# diskohedron4w_hermaphrodit.net
KiCad netlist of a schematic drawn in EAGLE
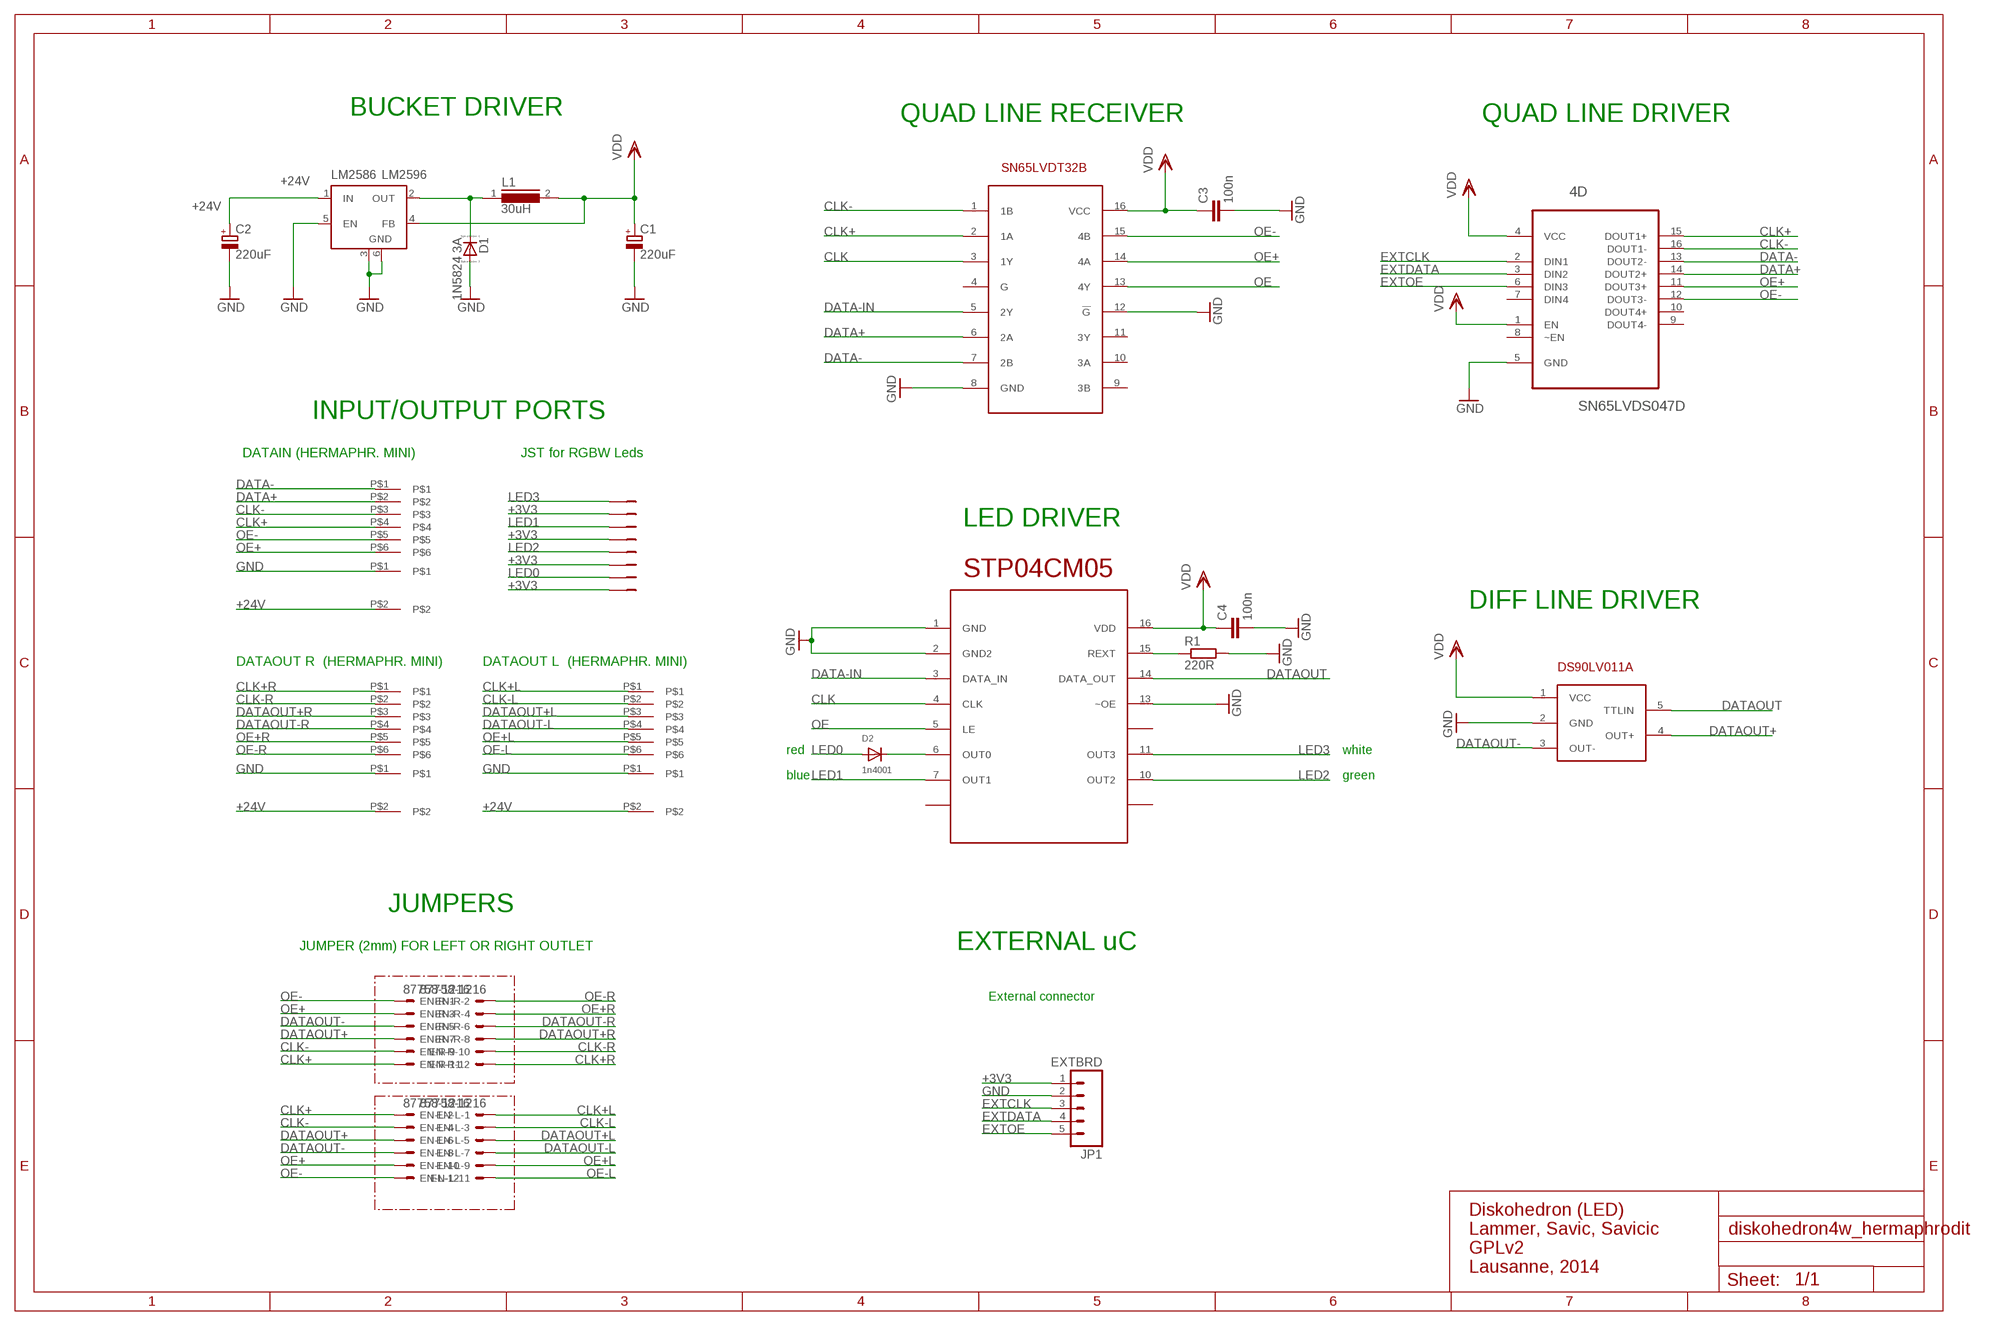
[diagram p0: schematic, sheet 1]

(export (version "E")
  (design (tool "Eeschema 10.0.6"))
  (components
    (comp (ref "1D")
      (value "DS90LV011A")
      (footprint "eagle-import:SOT23-5")
      (libsource (lib "eagle-import") (part "DS90LV011A"))
    )
    (comp (ref "4D")
      (value "SN65LVDS047D")
      (footprint "eagle-import:SOIC127P600X175-16N")
      (libsource (lib "eagle-import") (part "SN65LVDS047D"))
    )
    (comp (ref "4R")
      (value "SN65LVDST32")
      (footprint "eagle-import:SOIC16")
      (libsource (lib "eagle-import") (part "SN65LVDST32"))
    )
    (comp (ref "C1")
      (value "220uF")
      (footprint "eagle-import:153CLV-1010")
      (libsource (lib "eagle-import") (part "CPOL-EU153CLV-1010"))
    )
    (comp (ref "C2")
      (value "220uF")
      (footprint "eagle-import:153CLV-1010")
      (libsource (lib "eagle-import") (part "CPOL-EU153CLV-1010"))
    )
    (comp (ref "C3")
      (value "100n")
      (footprint "eagle-import:C0805")
      (libsource (lib "eagle-import") (part "C-EUC0805"))
    )
    (comp (ref "C4")
      (value "100n")
      (footprint "eagle-import:C0805")
      (libsource (lib "eagle-import") (part "C-EUC0805"))
    )
    (comp (ref "D1")
      (value "1N5824 3A")
      (footprint "eagle-import:DIODE_SMC")
      (libsource (lib "eagle-import") (part "DIODE_E-SMC"))
    )
    (comp (ref "D2")
      (value "1n4001")
      (footprint "eagle-import:SMADIODE")
      (libsource (lib "eagle-import") (part "DIODESMA"))
    )
    (comp (ref "EN-L")
      (value "87758-1216")
      (footprint "eagle-import:87758-1216")
      (libsource (lib "eagle-import") (part "87758-1216"))
    )
    (comp (ref "EN-R")
      (value "87758-1216")
      (footprint "eagle-import:87758-1216")
      (libsource (lib "eagle-import") (part "87758-1216"))
    )
    (comp (ref "IN1")
      (value "HERMAPHRODITMINI6PIN")
      (footprint "eagle-import:HERMAPHRODITMINI6PIN")
      (libsource (lib "eagle-import") (part "HERMAPHRODITMINI6PIN"))
    )
    (comp (ref "JP1")
      (value "EXTBRD")
      (footprint "eagle-import:1X05")
      (libsource (lib "eagle-import") (part "M05PTH"))
    )
    (comp (ref "JST")
      (value "8PIN-ZH")
      (footprint "eagle-import:B8B-ZH")
      (libsource (lib "eagle-import") (part "8PIN-ZH"))
    )
    (comp (ref "L1")
      (value "30uH")
      (footprint "eagle-import:DR127")
      (libsource (lib "eagle-import") (part "DR127"))
    )
    (comp (ref "LM2586")
      (value "LM2596")
      (footprint "eagle-import:TO263-5")
      (libsource (lib "eagle-import") (part "LM2596S"))
    )
    (comp (ref "OUT-L")
      (value "HERMAPHRODITMINI6PIN")
      (footprint "eagle-import:HERMAPHRODITMINI6PIN")
      (libsource (lib "eagle-import") (part "HERMAPHRODITMINI6PIN"))
    )
    (comp (ref "OUT-R")
      (value "HERMAPHRODITMINI6PIN")
      (footprint "eagle-import:HERMAPHRODITMINI6PIN")
      (libsource (lib "eagle-import") (part "HERMAPHRODITMINI6PIN"))
    )
    (comp (ref "R1")
      (value "220R")
      (footprint "eagle-import:M0805")
      (libsource (lib "eagle-import") (part "R-EU_M0805"))
    )
    (comp (ref "STP04")
      (value "STP04CM05")
      (footprint "eagle-import:TSSOP16")
      (libsource (lib "eagle-import") (part "STP04CM05"))
    )
    (comp (ref "U$6")
      (value "HERMAPHRODIT2PIN")
      (footprint "eagle-import:HERMAPHRODIT2PIN")
      (libsource (lib "eagle-import") (part "HERMAPHRODIT2PIN"))
    )
    (comp (ref "U$7")
      (value "HERMAPHRODIT2PIN")
      (footprint "eagle-import:HERMAPHRODIT2PIN")
      (libsource (lib "eagle-import") (part "HERMAPHRODIT2PIN"))
    )
    (comp (ref "U$12")
      (value "HERMAPHRODIT2PIN")
      (footprint "eagle-import:HERMAPHRODIT2PIN")
      (libsource (lib "eagle-import") (part "HERMAPHRODIT2PIN"))
    )
  )
  (nets
    (net (code "1") (name "/+24V") (class "Default")
      (node (ref "C2") (pin "+") (pinfunction "+_+") (pintype "passive"))
      (node (ref "LM2586") (pin "1") (pinfunction "IN_1") (pintype "input"))
      (node (ref "U$12") (pin "P$2") (pinfunction "P$2_P$2") (pintype "bidirectional"))
      (node (ref "U$6") (pin "P$2") (pinfunction "P$2_P$2") (pintype "bidirectional"))
      (node (ref "U$7") (pin "P$2") (pinfunction "P$2_P$2") (pintype "bidirectional"))
    )
    (net (code "2") (name "/CLK") (class "Default")
      (node (ref "4R") (pin "3") (pinfunction "1Y_3") (pintype "bidirectional"))
      (node (ref "STP04") (pin "4") (pinfunction "CLK_4") (pintype "bidirectional"))
    )
    (net (code "3") (name "/CLK+") (class "Default")
      (node (ref "4D") (pin "15") (pinfunction "DOUT1+_15") (pintype "output"))
      (node (ref "4R") (pin "2") (pinfunction "1A_2") (pintype "bidirectional"))
      (node (ref "EN-L") (pin "2") (pinfunction "S_2") (pintype "passive"))
      (node (ref "EN-R") (pin "11") (pinfunction "S_11") (pintype "passive"))
      (node (ref "IN1") (pin "P$4") (pinfunction "P$4_P$4") (pintype "bidirectional"))
    )
    (net (code "4") (name "/CLK+L") (class "Default")
      (node (ref "EN-L") (pin "1") (pinfunction "S_1") (pintype "passive"))
      (node (ref "OUT-L") (pin "P$1") (pinfunction "P$1_P$1") (pintype "bidirectional"))
    )
    (net (code "5") (name "/CLK+R") (class "Default")
      (node (ref "EN-R") (pin "12") (pinfunction "S_12") (pintype "passive"))
      (node (ref "OUT-R") (pin "P$1") (pinfunction "P$1_P$1") (pintype "bidirectional"))
    )
    (net (code "6") (name "/CLK-") (class "Default")
      (node (ref "4D") (pin "16") (pinfunction "DOUT1-_16") (pintype "output"))
      (node (ref "4R") (pin "1") (pinfunction "1B_1") (pintype "bidirectional"))
      (node (ref "EN-L") (pin "4") (pinfunction "S_4") (pintype "passive"))
      (node (ref "EN-R") (pin "9") (pinfunction "S_9") (pintype "passive"))
      (node (ref "IN1") (pin "P$3") (pinfunction "P$3_P$3") (pintype "bidirectional"))
    )
    (net (code "7") (name "/CLK-L") (class "Default")
      (node (ref "EN-L") (pin "3") (pinfunction "S_3") (pintype "passive"))
      (node (ref "OUT-L") (pin "P$2") (pinfunction "P$2_P$2") (pintype "bidirectional"))
    )
    (net (code "8") (name "/CLK-R") (class "Default")
      (node (ref "EN-R") (pin "10") (pinfunction "S_10") (pintype "passive"))
      (node (ref "OUT-R") (pin "P$2") (pinfunction "P$2_P$2") (pintype "bidirectional"))
    )
    (net (code "9") (name "/DATA+") (class "Default")
      (node (ref "4D") (pin "14") (pinfunction "DOUT2+_14") (pintype "output"))
      (node (ref "4R") (pin "6") (pinfunction "2A_6") (pintype "bidirectional"))
      (node (ref "IN1") (pin "P$2") (pinfunction "P$2_P$2") (pintype "bidirectional"))
    )
    (net (code "10") (name "/DATA-") (class "Default")
      (node (ref "4D") (pin "13") (pinfunction "DOUT2-_13") (pintype "output"))
      (node (ref "4R") (pin "7") (pinfunction "2B_7") (pintype "bidirectional"))
      (node (ref "IN1") (pin "P$1") (pinfunction "P$1_P$1") (pintype "bidirectional"))
    )
    (net (code "11") (name "/DATA-IN") (class "Default")
      (node (ref "4R") (pin "5") (pinfunction "2Y_5") (pintype "bidirectional"))
      (node (ref "STP04") (pin "3") (pinfunction "DATA_IN_3") (pintype "bidirectional"))
    )
    (net (code "12") (name "/DATAOUT") (class "Default")
      (node (ref "1D") (pin "5") (pinfunction "TTLIN_5") (pintype "bidirectional"))
      (node (ref "STP04") (pin "14") (pinfunction "DATA_OUT_14") (pintype "bidirectional"))
    )
    (net (code "13") (name "/DATAOUT+") (class "Default")
      (node (ref "1D") (pin "4") (pinfunction "OUT+_4") (pintype "bidirectional"))
      (node (ref "EN-L") (pin "6") (pinfunction "S_6") (pintype "passive"))
      (node (ref "EN-R") (pin "7") (pinfunction "S_7") (pintype "passive"))
    )
    (net (code "14") (name "/DATAOUT+L") (class "Default")
      (node (ref "EN-L") (pin "5") (pinfunction "S_5") (pintype "passive"))
      (node (ref "OUT-L") (pin "P$3") (pinfunction "P$3_P$3") (pintype "bidirectional"))
    )
    (net (code "15") (name "/DATAOUT+R") (class "Default")
      (node (ref "EN-R") (pin "8") (pinfunction "S_8") (pintype "passive"))
      (node (ref "OUT-R") (pin "P$3") (pinfunction "P$3_P$3") (pintype "bidirectional"))
    )
    (net (code "16") (name "/DATAOUT-") (class "Default")
      (node (ref "1D") (pin "3") (pinfunction "OUT-_3") (pintype "bidirectional"))
      (node (ref "EN-L") (pin "8") (pinfunction "S_8") (pintype "passive"))
      (node (ref "EN-R") (pin "5") (pinfunction "S_5") (pintype "passive"))
    )
    (net (code "17") (name "/DATAOUT-L") (class "Default")
      (node (ref "EN-L") (pin "7") (pinfunction "S_7") (pintype "passive"))
      (node (ref "OUT-L") (pin "P$4") (pinfunction "P$4_P$4") (pintype "bidirectional"))
    )
    (net (code "18") (name "/DATAOUT-R") (class "Default")
      (node (ref "EN-R") (pin "6") (pinfunction "S_6") (pintype "passive"))
      (node (ref "OUT-R") (pin "P$4") (pinfunction "P$4_P$4") (pintype "bidirectional"))
    )
    (net (code "19") (name "/EXTCLK") (class "Default")
      (node (ref "4D") (pin "2") (pinfunction "DIN1_2") (pintype "input"))
      (node (ref "JP1") (pin "3") (pinfunction "3_3") (pintype "passive"))
    )
    (net (code "20") (name "/EXTDATA") (class "Default")
      (node (ref "4D") (pin "3") (pinfunction "DIN2_3") (pintype "input"))
      (node (ref "JP1") (pin "4") (pinfunction "4_4") (pintype "passive"))
    )
    (net (code "21") (name "/EXTOE") (class "Default")
      (node (ref "4D") (pin "6") (pinfunction "DIN3_6") (pintype "input"))
      (node (ref "JP1") (pin "5") (pinfunction "5_5") (pintype "passive"))
    )
    (net (code "22") (name "/LED0") (class "Default")
      (node (ref "D2") (pin "A") (pinfunction "A_A") (pintype "passive"))
      (node (ref "JST") (pin "7") (pinfunction "1_7") (pintype "passive"))
    )
    (net (code "23") (name "/LED1") (class "Default")
      (node (ref "JST") (pin "3") (pinfunction "1_3") (pintype "passive"))
      (node (ref "STP04") (pin "7") (pinfunction "OUT1_7") (pintype "bidirectional"))
    )
    (net (code "24") (name "/LED2") (class "Default")
      (node (ref "JST") (pin "5") (pinfunction "1_5") (pintype "passive"))
      (node (ref "STP04") (pin "10") (pinfunction "OUT2_10") (pintype "bidirectional"))
    )
    (net (code "25") (name "/LED3") (class "Default")
      (node (ref "JST") (pin "1") (pinfunction "1_1") (pintype "passive"))
      (node (ref "STP04") (pin "11") (pinfunction "OUT3_11") (pintype "bidirectional"))
    )
    (net (code "26") (name "/OE") (class "Default")
      (node (ref "4R") (pin "13") (pinfunction "4Y_13") (pintype "bidirectional"))
      (node (ref "STP04") (pin "5") (pinfunction "LE_5") (pintype "bidirectional"))
    )
    (net (code "27") (name "/OE+") (class "Default")
      (node (ref "4D") (pin "11") (pinfunction "DOUT3+_11") (pintype "output"))
      (node (ref "4R") (pin "14") (pinfunction "4A_14") (pintype "bidirectional"))
      (node (ref "EN-L") (pin "10") (pinfunction "S_10") (pintype "passive"))
      (node (ref "EN-R") (pin "3") (pinfunction "S_3") (pintype "passive"))
      (node (ref "IN1") (pin "P$6") (pinfunction "P$6_P$6") (pintype "bidirectional"))
    )
    (net (code "28") (name "/OE+L") (class "Default")
      (node (ref "EN-L") (pin "9") (pinfunction "S_9") (pintype "passive"))
      (node (ref "OUT-L") (pin "P$5") (pinfunction "P$5_P$5") (pintype "bidirectional"))
    )
    (net (code "29") (name "/OE+R") (class "Default")
      (node (ref "EN-R") (pin "4") (pinfunction "S_4") (pintype "passive"))
      (node (ref "OUT-R") (pin "P$5") (pinfunction "P$5_P$5") (pintype "bidirectional"))
    )
    (net (code "30") (name "/OE-") (class "Default")
      (node (ref "4D") (pin "12") (pinfunction "DOUT3-_12") (pintype "output"))
      (node (ref "4R") (pin "15") (pinfunction "4B_15") (pintype "bidirectional"))
      (node (ref "EN-L") (pin "12") (pinfunction "S_12") (pintype "passive"))
      (node (ref "EN-R") (pin "1") (pinfunction "S_1") (pintype "passive"))
      (node (ref "IN1") (pin "P$5") (pinfunction "P$5_P$5") (pintype "bidirectional"))
    )
    (net (code "31") (name "/OE-L") (class "Default")
      (node (ref "EN-L") (pin "11") (pinfunction "S_11") (pintype "passive"))
      (node (ref "OUT-L") (pin "P$6") (pinfunction "P$6_P$6") (pintype "bidirectional"))
    )
    (net (code "32") (name "/OE-R") (class "Default")
      (node (ref "EN-R") (pin "2") (pinfunction "S_2") (pintype "passive"))
      (node (ref "OUT-R") (pin "P$6") (pinfunction "P$6_P$6") (pintype "bidirectional"))
    )
    (net (code "33") (name "GND") (class "Default")
      (node (ref "1D") (pin "2") (pinfunction "GND_2") (pintype "bidirectional"))
      (node (ref "4D") (pin "5") (pinfunction "GND_5") (pintype "passive"))
      (node (ref "4R") (pin "12") (pinfunction "~{G}_12") (pintype "bidirectional"))
      (node (ref "4R") (pin "8") (pinfunction "GND_8") (pintype "bidirectional"))
      (node (ref "C1") (pin "-") (pinfunction "-_-") (pintype "passive"))
      (node (ref "C2") (pin "-") (pinfunction "-_-") (pintype "passive"))
      (node (ref "C3") (pin "2") (pinfunction "2_2") (pintype "passive"))
      (node (ref "C4") (pin "2") (pinfunction "2_2") (pintype "passive"))
      (node (ref "D1") (pin "A") (pinfunction "C_A") (pintype "passive"))
      (node (ref "JP1") (pin "2") (pinfunction "2_2") (pintype "passive"))
      (node (ref "LM2586") (pin "3") (pinfunction "GND_3") (pintype "power_in"))
      (node (ref "LM2586") (pin "5") (pinfunction "EN_5") (pintype "input"))
      (node (ref "LM2586") (pin "6") (pinfunction "GND_6") (pintype "power_in"))
      (node (ref "R1") (pin "2") (pinfunction "2_2") (pintype "passive"))
      (node (ref "STP04") (pin "1") (pinfunction "GND_1") (pintype "bidirectional"))
      (node (ref "STP04") (pin "13") (pinfunction "~{OE}_13") (pintype "bidirectional"))
      (node (ref "STP04") (pin "2") (pinfunction "GND2_2") (pintype "bidirectional"))
      (node (ref "U$12") (pin "P$1") (pinfunction "P$1_P$1") (pintype "bidirectional"))
      (node (ref "U$6") (pin "P$1") (pinfunction "P$1_P$1") (pintype "bidirectional"))
      (node (ref "U$7") (pin "P$1") (pinfunction "P$1_P$1") (pintype "bidirectional"))
    )
    (net (code "34") (name "Net-(D1-A)") (class "Default")
      (node (ref "D1") (pin "C") (pinfunction "A_C") (pintype "passive"))
      (node (ref "L1") (pin "1") (pinfunction "1_1") (pintype "passive"))
      (node (ref "LM2586") (pin "2") (pinfunction "OUT_2") (pintype "output"))
    )
    (net (code "35") (name "Net-(STP04-OUT0)") (class "Default")
      (node (ref "D2") (pin "C") (pinfunction "C_C") (pintype "passive"))
      (node (ref "STP04") (pin "6") (pinfunction "OUT0_6") (pintype "bidirectional"))
    )
    (net (code "36") (name "Net-(STP04-REXT)") (class "Default")
      (node (ref "R1") (pin "1") (pinfunction "1_1") (pintype "passive"))
      (node (ref "STP04") (pin "15") (pinfunction "REXT_15") (pintype "bidirectional"))
    )
    (net (code "37") (name "VDD") (class "Default")
      (node (ref "1D") (pin "1") (pinfunction "VCC_1") (pintype "bidirectional"))
      (node (ref "4D") (pin "1") (pinfunction "EN_1") (pintype "input"))
      (node (ref "4D") (pin "4") (pinfunction "VCC_4") (pintype "power_in"))
      (node (ref "4R") (pin "16") (pinfunction "VCC_16") (pintype "bidirectional"))
      (node (ref "C1") (pin "+") (pinfunction "+_+") (pintype "passive"))
      (node (ref "C3") (pin "1") (pinfunction "1_1") (pintype "passive"))
      (node (ref "C4") (pin "1") (pinfunction "1_1") (pintype "passive"))
      (node (ref "JP1") (pin "1") (pinfunction "1_1") (pintype "passive"))
      (node (ref "JST") (pin "2") (pinfunction "1_2") (pintype "passive"))
      (node (ref "JST") (pin "4") (pinfunction "1_4") (pintype "passive"))
      (node (ref "JST") (pin "6") (pinfunction "1_6") (pintype "passive"))
      (node (ref "JST") (pin "8") (pinfunction "1_8") (pintype "passive"))
      (node (ref "L1") (pin "2") (pinfunction "2_2") (pintype "passive"))
      (node (ref "LM2586") (pin "4") (pinfunction "FB_4") (pintype "input"))
      (node (ref "STP04") (pin "16") (pinfunction "VDD_16") (pintype "bidirectional"))
    )
    (net (code "38") (name "unconnected-(4D-DIN4-Pad7)") (class "Default")
      (node (ref "4D") (pin "7") (pinfunction "DIN4_7") (pintype "input"))
    )
    (net (code "39") (name "unconnected-(4D-DOUT4+-Pad10)") (class "Default")
      (node (ref "4D") (pin "10") (pinfunction "DOUT4+_10") (pintype "output"))
    )
    (net (code "40") (name "unconnected-(4D-DOUT4--Pad9)") (class "Default")
      (node (ref "4D") (pin "9") (pinfunction "DOUT4-_9") (pintype "output"))
    )
    (net (code "41") (name "unconnected-(4D-~{EN}-Pad8)") (class "Default")
      (node (ref "4D") (pin "8") (pinfunction "~{EN}_8") (pintype "input"))
    )
    (net (code "42") (name "unconnected-(4R-3A-Pad10)") (class "Default")
      (node (ref "4R") (pin "10") (pinfunction "3A_10") (pintype "bidirectional"))
    )
    (net (code "43") (name "unconnected-(4R-3B-Pad9)") (class "Default")
      (node (ref "4R") (pin "9") (pinfunction "3B_9") (pintype "bidirectional"))
    )
    (net (code "44") (name "unconnected-(4R-3Y-Pad11)") (class "Default")
      (node (ref "4R") (pin "11") (pinfunction "3Y_11") (pintype "bidirectional"))
    )
    (net (code "45") (name "unconnected-(4R-G-Pad4)") (class "Default")
      (node (ref "4R") (pin "4") (pinfunction "G_4") (pintype "bidirectional"))
    )
    (net (code "46") (name "unconnected-(STP04-N.C1-Pad8)") (class "Default")
      (node (ref "STP04") (pin "8") (pinfunction "N.C1_8") (pintype "bidirectional"))
    )
    (net (code "47") (name "unconnected-(STP04-NC-Pad9)") (class "Default")
      (node (ref "STP04") (pin "9") (pinfunction "NC_9") (pintype "bidirectional"))
    )
    (net (code "48") (name "unconnected-(STP04-NC3-Pad12)") (class "Default")
      (node (ref "STP04") (pin "12") (pinfunction "NC3_12") (pintype "bidirectional"))
    )
  )
)
